# power.net
KiCad netlist of a schematic drawn in Altium Designer
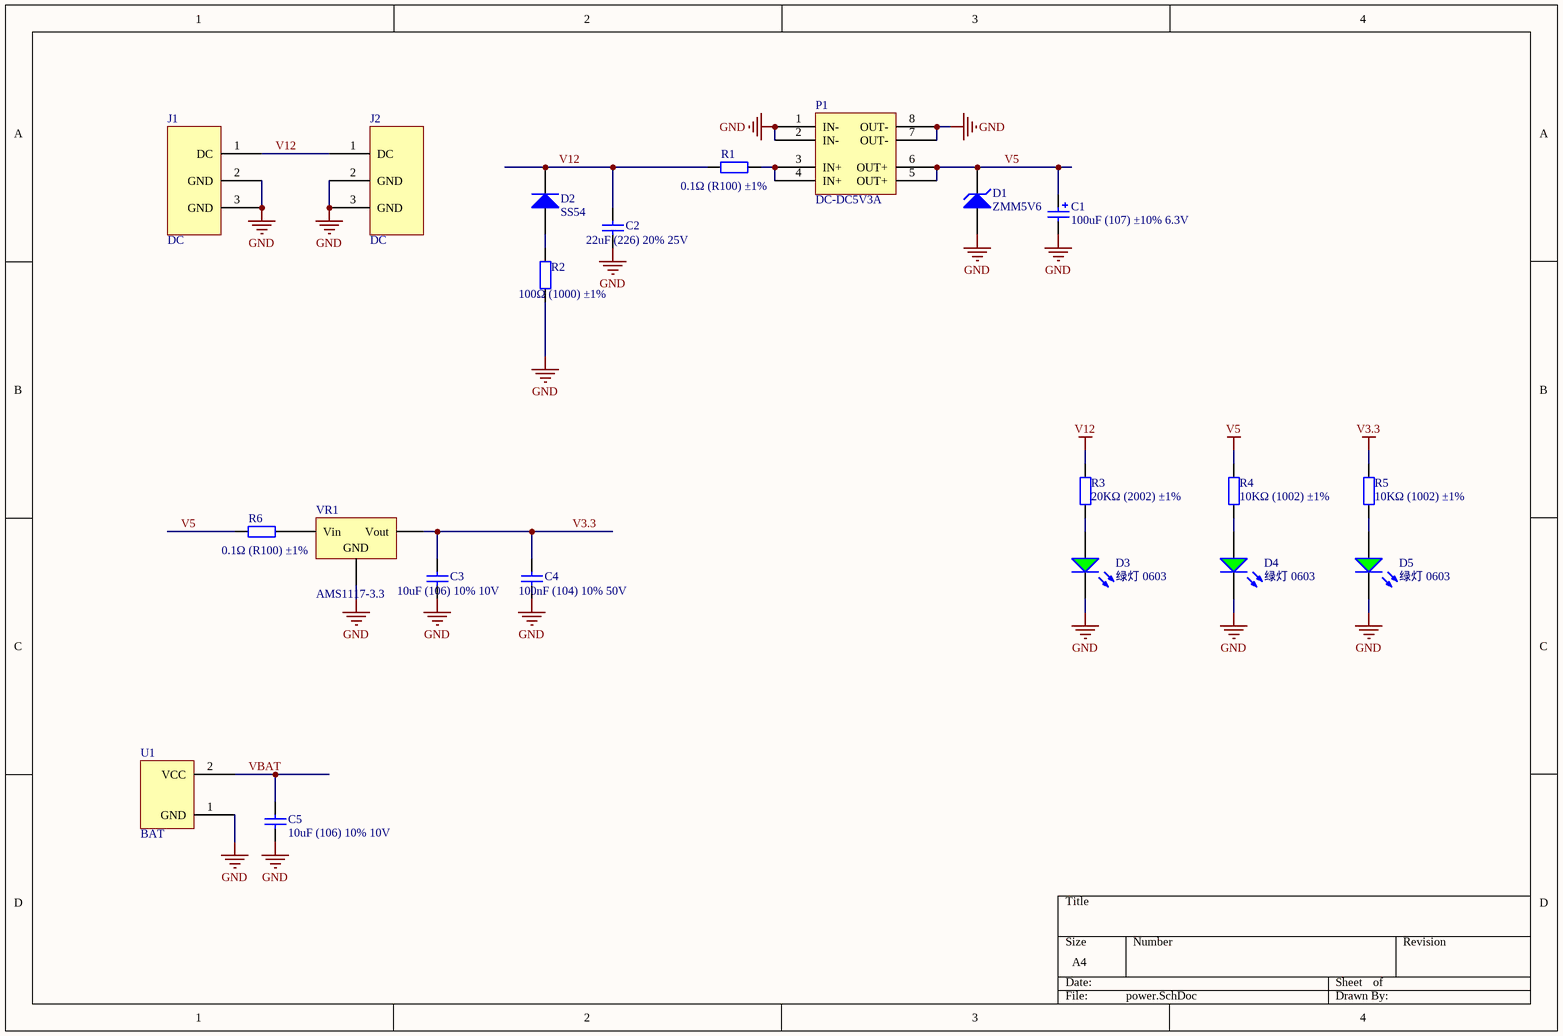
[diagram p0: power.SchDoc]

(export (version "E")
  (design (tool "Eeschema 10.0.6"))
  (components
    (comp (ref "C1")
      (value "100uF (107) ±10% 6.3V")
      (footprint "CASE-B_3528")
      (description "钽电容")
      (libsource (lib "Miscellaneous Devices LC") (part "3528 100uF (107) 10% 6.3V"))
    )
    (comp (ref "C2")
      (value "22uF (226) 20% 25V")
      (footprint "0805_C")
      (description "贴片电容")
      (libsource (lib "Miscellaneous Devices LC") (part "0805 22uF (226) 20% 25V"))
    )
    (comp (ref "C3")
      (value "10uF (106) 10% 10V")
      (footprint "0603_C")
      (description "贴片电容")
      (libsource (lib "Miscellaneous Devices LC") (part "0603 10uF (106) 10% 10V"))
    )
    (comp (ref "C4")
      (value "100nF (104) 10% 50V")
      (footprint "0603_C")
      (description "贴片电容")
      (libsource (lib "Miscellaneous Devices LC") (part "0603 100nF (104) 10% 50V"))
    )
    (comp (ref "C5")
      (value "10uF (106) 10% 10V")
      (footprint "0603_C")
      (description "贴片电容")
      (libsource (lib "Miscellaneous Devices LC") (part "0603 10uF (106) 10% 10V"))
    )
    (comp (ref "D1")
      (value "ZMM5V6")
      (footprint "LL-34")
      (description "稳压二极管")
      (libsource (lib "Miscellaneous Devices LC") (part "LL-34 ZMM5V6"))
    )
    (comp (ref "D2")
      (value "SS54")
      (footprint "SMA(DO-214AC)_S1")
      (description "二极管")
      (libsource (lib "Miscellaneous Devices LC") (part "SMA(DO-214AC) SS54"))
    )
    (comp (ref "D3")
      (value "绿灯 0603")
      (footprint "0603_LED_S1")
      (description "发光二极管")
      (libsource (lib "Miscellaneous Devices LC") (part "0603 绿灯"))
    )
    (comp (ref "D4")
      (value "绿灯 0603")
      (footprint "0603_LED_S1")
      (description "发光二极管")
      (libsource (lib "Miscellaneous Devices LC") (part "0603 绿灯"))
    )
    (comp (ref "D5")
      (value "绿灯 0603")
      (footprint "0603_LED_S1")
      (description "发光二极管")
      (libsource (lib "Miscellaneous Devices LC") (part "0603 绿灯"))
    )
    (comp (ref "J1")
      (value "DC")
      (footprint "DC005")
      (description "Connector for DC 12V")
      (libsource (lib "") (part "DC_1"))
    )
    (comp (ref "J2")
      (value "DC")
      (footprint "DC005")
      (description "Connector for DC 12V")
      (libsource (lib "CHK-I") (part "DC"))
    )
    (comp (ref "P1") (value "DC-DC5V3A") (footprint "DC-DC3A") (libsource (lib "CHK-I") (part "DC-DC3A")))
    (comp (ref "R1")
      (value "0.1Ω (R100) ±1%")
      (footprint "1206_R")
      (description "贴片电阻")
      (libsource (lib "Miscellaneous Devices LC") (part "1206 0.1Ω (R100) 1%"))
    )
    (comp (ref "R2")
      (value "100Ω (1000) ±1%")
      (footprint "0805_R")
      (description "贴片电阻")
      (libsource (lib "Miscellaneous Devices LC") (part "0805 100Ω (1000) 1%"))
    )
    (comp (ref "R3")
      (value "20KΩ (2002) ±1%")
      (footprint "0603_R")
      (description "贴片电阻")
      (libsource (lib "Miscellaneous Devices LC") (part "0603 20KΩ (2002) 1%"))
    )
    (comp (ref "R4")
      (value "10KΩ (1002) ±1%")
      (footprint "0603_R")
      (description "贴片电阻")
      (libsource (lib "Miscellaneous Devices LC") (part "0603 10KΩ (1002) 1%"))
    )
    (comp (ref "R5")
      (value "10KΩ (1002) ±1%")
      (footprint "0603_R")
      (description "贴片电阻")
      (libsource (lib "Miscellaneous Devices LC") (part "0603 10KΩ (1002) 1%"))
    )
    (comp (ref "R6")
      (value "0.1Ω (R100) ±1%")
      (footprint "1206_R")
      (description "贴片电阻")
      (libsource (lib "Miscellaneous Devices LC") (part "1206 0.1Ω (R100) 1%"))
    )
    (comp (ref "U1") (value "BAT") (footprint "BAT2032") (libsource (lib "CHK-I") (part "BAT2032")))
    (comp (ref "VR1")
      (value "AMS1117-3.3")
      (footprint "SOT-223")
      (description "低压差线性稳压(LDO)")
      (libsource (lib "Miscellaneous Devices LC") (part "SOT-223 AMS1117-3.3"))
    )
  )
  (nets
    (net (code "1") (name "/VBAT") (class "Default")
      (node (ref "C5") (pin "2") (pinfunction "2_2") (pintype "passive"))
      (node (ref "U1") (pin "2") (pinfunction "VCC_2") (pintype "passive"))
    )
    (net (code "2") (name "GND") (class "Default")
      (node (ref "C1") (pin "2") (pinfunction "2_2") (pintype "passive"))
      (node (ref "C2") (pin "1") (pinfunction "1_1") (pintype "passive"))
      (node (ref "C3") (pin "1") (pinfunction "1_1") (pintype "passive"))
      (node (ref "C4") (pin "1") (pinfunction "1_1") (pintype "passive"))
      (node (ref "C5") (pin "1") (pinfunction "1_1") (pintype "passive"))
      (node (ref "D1") (pin "1") (pinfunction "A_1") (pintype "passive"))
      (node (ref "D3") (pin "K") (pinfunction "K_K") (pintype "passive"))
      (node (ref "D4") (pin "K") (pinfunction "K_K") (pintype "passive"))
      (node (ref "D5") (pin "K") (pinfunction "K_K") (pintype "passive"))
      (node (ref "J1") (pin "2") (pinfunction "GND_2") (pintype "passive"))
      (node (ref "J1") (pin "3") (pinfunction "GND_3") (pintype "passive"))
      (node (ref "J2") (pin "2") (pinfunction "GND_2") (pintype "passive"))
      (node (ref "J2") (pin "3") (pinfunction "GND_3") (pintype "passive"))
      (node (ref "P1") (pin "1") (pinfunction "IN-_1") (pintype "passive"))
      (node (ref "P1") (pin "2") (pinfunction "IN-_2") (pintype "passive"))
      (node (ref "P1") (pin "7") (pinfunction "OUT-_7") (pintype "passive"))
      (node (ref "P1") (pin "8") (pinfunction "OUT-_8") (pintype "passive"))
      (node (ref "R2") (pin "1") (pinfunction "1_1") (pintype "passive"))
      (node (ref "U1") (pin "1") (pinfunction "GND_1") (pintype "passive"))
      (node (ref "VR1") (pin "1") (pinfunction "GND_1") (pintype "passive"))
    )
    (net (code "3") (name "Net-(D2-A)") (class "Default")
      (node (ref "D2") (pin "1") (pinfunction "A_1") (pintype "passive"))
      (node (ref "R2") (pin "2") (pinfunction "2_2") (pintype "passive"))
    )
    (net (code "4") (name "Net-(D3-PadA)") (class "Default")
      (node (ref "D3") (pin "A") (pinfunction "A_A") (pintype "passive"))
      (node (ref "R3") (pin "1") (pinfunction "1_1") (pintype "passive"))
    )
    (net (code "5") (name "Net-(D4-PadA)") (class "Default")
      (node (ref "D4") (pin "A") (pinfunction "A_A") (pintype "passive"))
      (node (ref "R4") (pin "1") (pinfunction "1_1") (pintype "passive"))
    )
    (net (code "6") (name "Net-(D5-PadA)") (class "Default")
      (node (ref "D5") (pin "A") (pinfunction "A_A") (pintype "passive"))
      (node (ref "R5") (pin "1") (pinfunction "1_1") (pintype "passive"))
    )
    (net (code "7") (name "Net-(P1-IN+-Pad3)") (class "Default")
      (node (ref "P1") (pin "3") (pinfunction "IN+_3") (pintype "passive"))
      (node (ref "P1") (pin "4") (pinfunction "IN+_4") (pintype "passive"))
      (node (ref "R1") (pin "2") (pinfunction "2_2") (pintype "passive"))
    )
    (net (code "8") (name "Net-(VR1-Vin)") (class "Default")
      (node (ref "R6") (pin "2") (pinfunction "2_2") (pintype "passive"))
      (node (ref "VR1") (pin "3") (pinfunction "Vin_3") (pintype "passive"))
    )
    (net (code "9") (name "V3.3") (class "Default")
      (node (ref "C3") (pin "2") (pinfunction "2_2") (pintype "passive"))
      (node (ref "C4") (pin "2") (pinfunction "2_2") (pintype "passive"))
      (node (ref "R5") (pin "2") (pinfunction "2_2") (pintype "passive"))
      (node (ref "VR1") (pin "2") (pinfunction "Vout_2") (pintype "passive"))
    )
    (net (code "10") (name "V5") (class "Default")
      (node (ref "C1") (pin "1") (pinfunction "1_1") (pintype "passive"))
      (node (ref "D1") (pin "2") (pinfunction "K_2") (pintype "passive"))
      (node (ref "P1") (pin "5") (pinfunction "OUT+_5") (pintype "passive"))
      (node (ref "P1") (pin "6") (pinfunction "OUT+_6") (pintype "passive"))
      (node (ref "R4") (pin "2") (pinfunction "2_2") (pintype "passive"))
      (node (ref "R6") (pin "1") (pinfunction "1_1") (pintype "passive"))
    )
    (net (code "11") (name "V12") (class "Default")
      (node (ref "C2") (pin "2") (pinfunction "2_2") (pintype "passive"))
      (node (ref "D2") (pin "2") (pinfunction "K_2") (pintype "passive"))
      (node (ref "J1") (pin "1") (pinfunction "DC_1") (pintype "passive"))
      (node (ref "J2") (pin "1") (pinfunction "DC_1") (pintype "passive"))
      (node (ref "R1") (pin "1") (pinfunction "1_1") (pintype "passive"))
      (node (ref "R3") (pin "2") (pinfunction "2_2") (pintype "passive"))
    )
  )
)
